# Schema.net
KiCad netlist of a schematic drawn in EAGLE
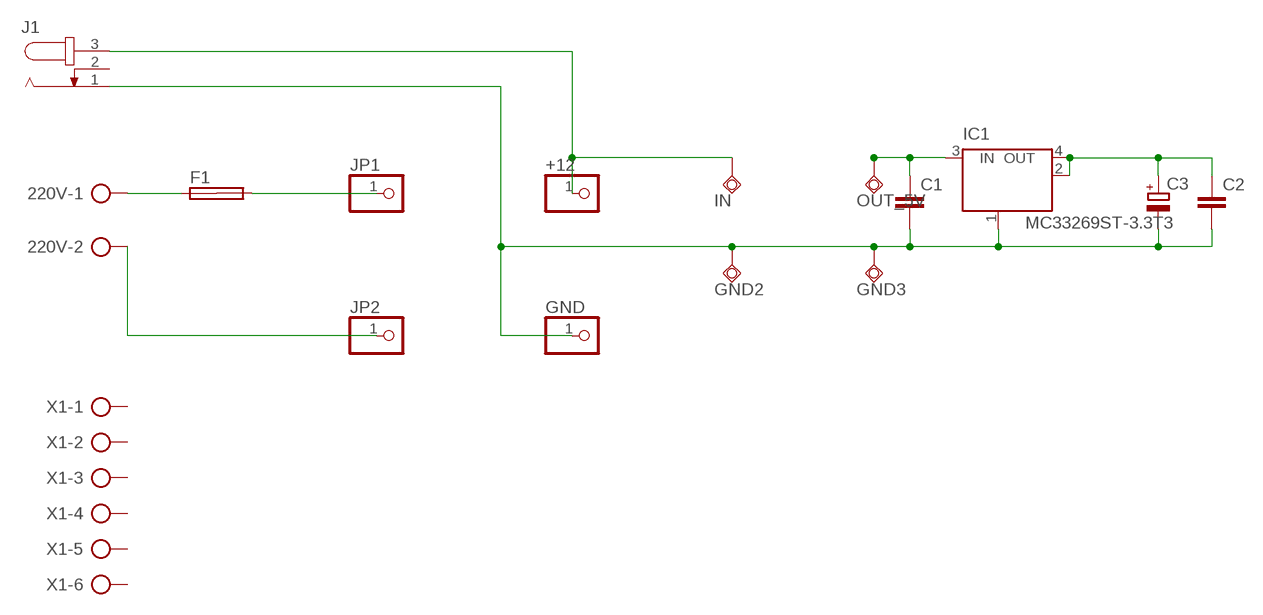
[diagram p0: schematic, sheet 1]

(export (version "E")
  (design (tool "Eeschema 10.0.6"))
  (components
    (comp (ref "+12")
      (value "PINHD-1X1")
      (footprint "eagle-import:1X01")
      (libsource (lib "eagle-import") (part "PINHD-1X1"))
    )
    (comp (ref "220V")
      (value "AK500/2")
      (footprint "eagle-import:AK500_2")
      (libsource (lib "eagle-import") (part "AK500/2"))
    )
    (comp (ref "C1")
      (value "C-EUC2012")
      (footprint "eagle-import:C2012")
      (libsource (lib "eagle-import") (part "C-EUC2012"))
    )
    (comp (ref "C2")
      (value "C-EUC2012")
      (footprint "eagle-import:C2012")
      (libsource (lib "eagle-import") (part "C-EUC2012"))
    )
    (comp (ref "C3")
      (value "CPOL-EUE2.5-5")
      (footprint "eagle-import:E2,5-5")
      (libsource (lib "eagle-import") (part "CPOL-EUE2.5-5"))
    )
    (comp (ref "F1")
      (value "SH32")
      (footprint "eagle-import:SH32")
      (fields (field (name "MPN") "10207101009"))
      (libsource (lib "eagle-import") (part "SH32"))
    )
    (comp (ref "GND")
      (value "PINHD-1X1")
      (footprint "eagle-import:1X01")
      (libsource (lib "eagle-import") (part "PINHD-1X1"))
    )
    (comp (ref "GND2")
      (value "TPSQTP20SQ")
      (footprint "eagle-import:TP20SQ")
      (libsource (lib "eagle-import") (part "TPSQTP20SQ"))
    )
    (comp (ref "GND3")
      (value "TPSQTP20SQ")
      (footprint "eagle-import:TP20SQ")
      (libsource (lib "eagle-import") (part "TPSQTP20SQ"))
    )
    (comp (ref "IC1")
      (value "MC33269ST-3.3T3")
      (footprint "eagle-import:SOT223")
      (libsource (lib "eagle-import") (part "MC33269ST-3.3T3"))
    )
    (comp (ref "IN")
      (value "TPSQTP20SQ")
      (footprint "eagle-import:TP20SQ")
      (libsource (lib "eagle-import") (part "TPSQTP20SQ"))
    )
    (comp (ref "J1")
      (value "JACK-PLUG1")
      (footprint "eagle-import:SPC4078")
      (libsource (lib "eagle-import") (part "JACK-PLUG1"))
    )
    (comp (ref "JP1")
      (value "PINHD-1X1")
      (footprint "eagle-import:1X01")
      (libsource (lib "eagle-import") (part "PINHD-1X1"))
    )
    (comp (ref "JP2")
      (value "PINHD-1X1")
      (footprint "eagle-import:1X01")
      (libsource (lib "eagle-import") (part "PINHD-1X1"))
    )
    (comp (ref "OUT_5V")
      (value "TPSQTP20SQ")
      (footprint "eagle-import:TP20SQ")
      (libsource (lib "eagle-import") (part "TPSQTP20SQ"))
    )
    (comp (ref "X1")
      (value "AK500/6")
      (footprint "eagle-import:AK500_6")
      (libsource (lib "eagle-import") (part "AK500/6"))
    )
  )
  (nets
    (net (code "1") (name "Net-(+12-Pad1)") (class "Default")
      (node (ref "+12") (pin "1") (pinfunction "1_1") (pintype "passive"))
      (node (ref "IN") (pin "TP") (pinfunction "TP_TP") (pintype "input"))
      (node (ref "J1") (pin "3") (pinfunction "3_3") (pintype "passive"))
    )
    (net (code "2") (name "Net-(220VA-KL)") (class "Default")
      (node (ref "220V") (pin "1") (pinfunction "KL_1") (pintype "passive"))
      (node (ref "F1") (pin "1A") (pinfunction "1A_1A") (pintype "passive"))
    )
    (net (code "3") (name "Net-(220VB-KL)") (class "Default")
      (node (ref "220V") (pin "2") (pinfunction "KL_2") (pintype "passive"))
      (node (ref "JP2") (pin "1") (pinfunction "1_1") (pintype "passive"))
    )
    (net (code "4") (name "Net-(C2-Pad1)") (class "Default")
      (node (ref "C2") (pin "1") (pinfunction "1_1") (pintype "passive"))
      (node (ref "C3") (pin "+") (pinfunction "+_+") (pintype "passive"))
      (node (ref "IC1") (pin "2") (pinfunction "OUT_2") (pintype "passive"))
      (node (ref "IC1") (pin "4") (pinfunction "OUT_4") (pintype "passive"))
    )
    (net (code "5") (name "Net-(F1-Pad2A)") (class "Default")
      (node (ref "F1") (pin "2A") (pinfunction "2A_2A") (pintype "passive"))
      (node (ref "JP1") (pin "1") (pinfunction "1_1") (pintype "passive"))
    )
    (net (code "6") (name "Net-(IC1-GND{slash}ADJ)") (class "Default")
      (node (ref "C1") (pin "2") (pinfunction "2_2") (pintype "passive"))
      (node (ref "C2") (pin "2") (pinfunction "2_2") (pintype "passive"))
      (node (ref "C3") (pin "-") (pinfunction "-_-") (pintype "passive"))
      (node (ref "GND") (pin "1") (pinfunction "1_1") (pintype "passive"))
      (node (ref "GND2") (pin "TP") (pinfunction "TP_TP") (pintype "input"))
      (node (ref "GND3") (pin "TP") (pinfunction "TP_TP") (pintype "input"))
      (node (ref "IC1") (pin "1") (pinfunction "GND/ADJ_1") (pintype "input"))
      (node (ref "J1") (pin "1") (pinfunction "1_1") (pintype "passive"))
    )
    (net (code "7") (name "Net-(IC1-IN)") (class "Default")
      (node (ref "C1") (pin "1") (pinfunction "1_1") (pintype "passive"))
      (node (ref "IC1") (pin "3") (pinfunction "IN_3") (pintype "input"))
      (node (ref "OUT_5V") (pin "TP") (pinfunction "TP_TP") (pintype "input"))
    )
    (net (code "8") (name "unconnected-(F1-Pad1B)") (class "Default")
      (node (ref "F1") (pin "1B") (pinfunction "1B_1B") (pintype "passive"))
    )
    (net (code "9") (name "unconnected-(F1-Pad2B)") (class "Default")
      (node (ref "F1") (pin "2B") (pinfunction "2B_2B") (pintype "passive"))
    )
    (net (code "10") (name "unconnected-(J1-Pad2)") (class "Default")
      (node (ref "J1") (pin "2") (pinfunction "2_2") (pintype "passive"))
    )
    (net (code "11") (name "unconnected-(X1A-KL-Pad1)") (class "Default")
      (node (ref "X1") (pin "1") (pinfunction "KL_1") (pintype "passive"))
    )
    (net (code "12") (name "unconnected-(X1B-KL-Pad2)") (class "Default")
      (node (ref "X1") (pin "2") (pinfunction "KL_2") (pintype "passive"))
    )
    (net (code "13") (name "unconnected-(X1C-KL-Pad3)") (class "Default")
      (node (ref "X1") (pin "3") (pinfunction "KL_3") (pintype "passive"))
    )
    (net (code "14") (name "unconnected-(X1D-KL-Pad4)") (class "Default")
      (node (ref "X1") (pin "4") (pinfunction "KL_4") (pintype "passive"))
    )
    (net (code "15") (name "unconnected-(X1E-KL-Pad5)") (class "Default")
      (node (ref "X1") (pin "5") (pinfunction "KL_5") (pintype "passive"))
    )
    (net (code "16") (name "unconnected-(X1F-KL-Pad6)") (class "Default")
      (node (ref "X1") (pin "6") (pinfunction "KL_6") (pintype "passive"))
    )
  )
)
